# 1608_-_3.net
KiCad netlist of a schematic drawn in Altium Designer
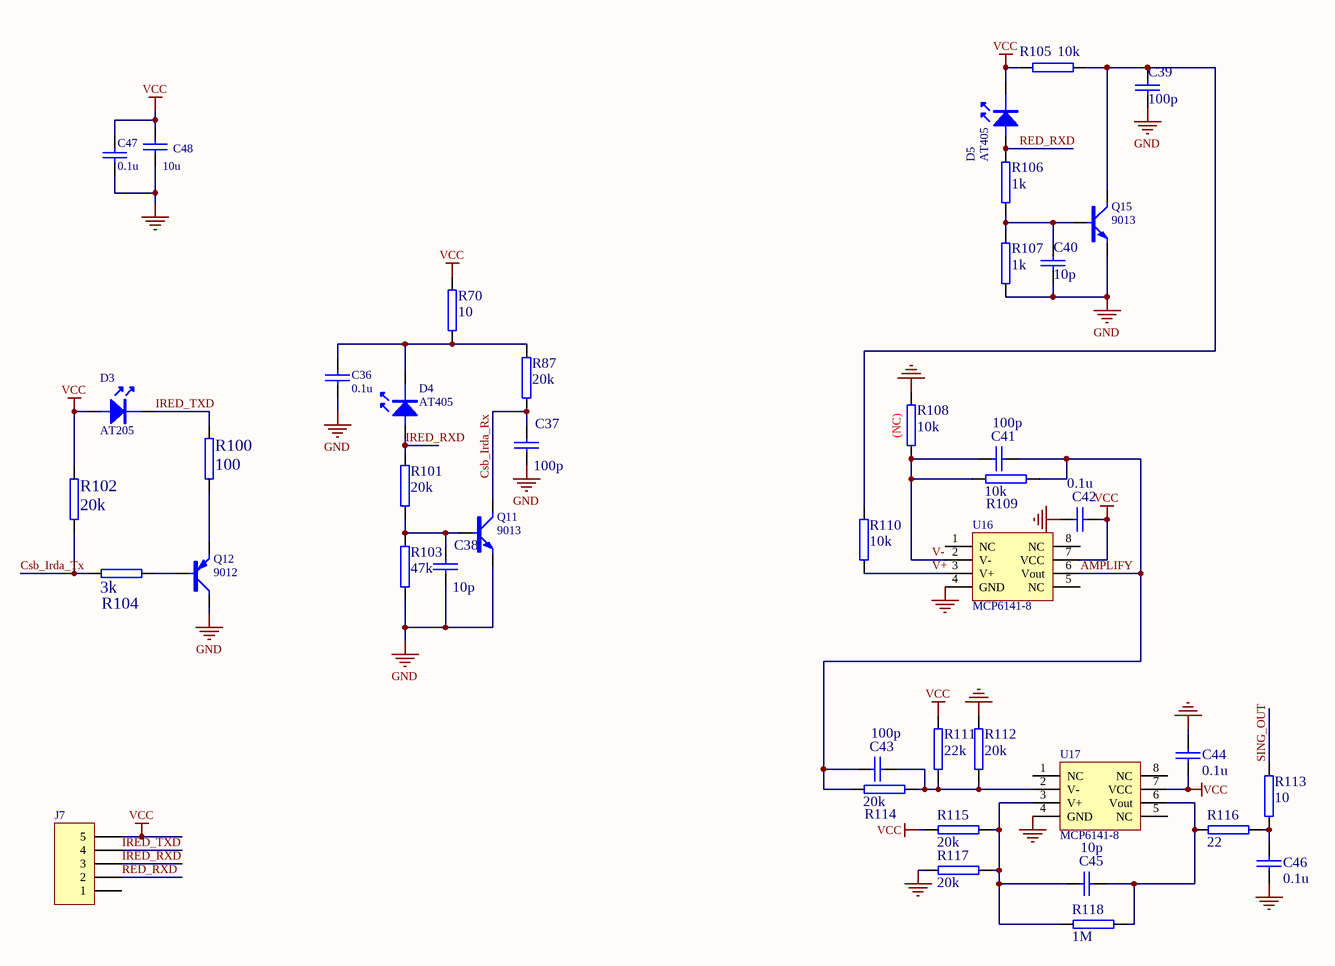
[diagram p0: 1608卡-原理图3.SchDoc]

(export (version "E")
  (design (tool "Eeschema 10.0.6"))
  (components
    (comp (ref "C36")
      (value "0.1u")
      (footprint "C0603")
      (description "无极性电容")
      (libsource (lib "CBB_Lib_SCH") (part "CAP"))
    )
    (comp (ref "C37")
      (value "100p")
      (footprint "C0603")
      (description "Capacitor")
      (libsource (lib "*") (part "CAP"))
    )
    (comp (ref "C38")
      (value "10p")
      (footprint "C0603")
      (description "Capacitor")
      (libsource (lib "*") (part "CAP"))
    )
    (comp (ref "C39")
      (value "100p")
      (footprint "C0603")
      (description "Capacitor")
      (libsource (lib "*") (part "CAP"))
    )
    (comp (ref "C40")
      (value "10p")
      (footprint "C0603")
      (description "Capacitor")
      (libsource (lib "*") (part "CAP"))
    )
    (comp (ref "C41")
      (value "100p")
      (footprint "C0603")
      (description "Capacitor")
      (libsource (lib "*") (part "CAP"))
    )
    (comp (ref "C42")
      (value "0.1u")
      (footprint "C0603")
      (description "Capacitor")
      (libsource (lib "*") (part "CAP"))
    )
    (comp (ref "C43")
      (value "100p")
      (footprint "C0603")
      (description "Capacitor")
      (libsource (lib "*") (part "CAP"))
    )
    (comp (ref "C44")
      (value "0.1u")
      (footprint "C0603")
      (description "Capacitor")
      (libsource (lib "*") (part "CAP"))
    )
    (comp (ref "C45")
      (value "10p")
      (footprint "C0603")
      (description "Capacitor")
      (libsource (lib "*") (part "CAP"))
    )
    (comp (ref "C46")
      (value "0.1u")
      (footprint "C0603")
      (description "Capacitor")
      (libsource (lib "*") (part "CAP"))
    )
    (comp (ref "C47")
      (value "0.1u")
      (footprint "C0603")
      (description "无极性电容")
      (libsource (lib "CBB_Lib_SCH") (part "CAP"))
    )
    (comp (ref "C48")
      (value "10u")
      (footprint "C0603")
      (description "无极性电容")
      (libsource (lib "CBB_Lib_SCH") (part "CAP"))
    )
    (comp (ref "D3") (value "AT205") (footprint "LEDRED") (libsource (lib "chip") (part "LED-5")))
    (comp (ref "D4") (value "AT405") (footprint "LEDRED") (libsource (lib "chip") (part "LED-5")))
    (comp (ref "D5") (value "AT405") (footprint "LEDRED") (libsource (lib "chip") (part "LED-5")))
    (comp (ref "J7")
      (value "TEM")
      (footprint "JP5")
      (description "Header, 5-Pin")
      (fields (field (name "PUBLISHER") "Altium Limited"))
      (libsource (lib "Miscellaneous Connectors") (part "Header 5"))
    )
    (comp (ref "Q11")
      (value "9013")
      (footprint "CBB_Lib_PCB:SOT-23-TRAN")
      (description "NPN Transistor")
      (libsource (lib "CBB_Lib_SCH") (part "NPN-S"))
    )
    (comp (ref "Q12") (value "9012") (footprint "SOT23-9013") (libsource (lib "chip") (part "9012")))
    (comp (ref "Q15")
      (value "9013")
      (footprint "CBB_Lib_PCB:SOT-23-TRAN")
      (description "NPN Transistor")
      (libsource (lib "CBB_Lib_SCH") (part "NPN-S"))
    )
    (comp (ref "R70") (value "10") (footprint "R0603") (libsource (lib "*") (part "RES11")))
    (comp (ref "R87") (value "20k") (footprint "R0603") (libsource (lib "*") (part "RES11")))
    (comp (ref "R100") (value "100") (footprint "R0603") (libsource (lib "*") (part "Pro28.tmp_UnNamed_37")))
    (comp (ref "R101") (value "20k") (footprint "R0603") (libsource (lib "*") (part "RES11")))
    (comp (ref "R102") (value "20k") (footprint "R0603") (libsource (lib "*") (part "Pro28.tmp_UnNamed_37")))
    (comp (ref "R103") (value "47k") (footprint "R0603") (libsource (lib "*") (part "RES11")))
    (comp (ref "R104") (value "3k") (footprint "R0603") (libsource (lib "*") (part "Pro28.tmp_UnNamed_37")))
    (comp (ref "R105") (value "10k") (footprint "R0603") (libsource (lib "*") (part "RES11")))
    (comp (ref "R106") (value "1k") (footprint "R0603") (libsource (lib "*") (part "RES11")))
    (comp (ref "R107") (value "1k") (footprint "R0603") (libsource (lib "*") (part "RES11")))
    (comp (ref "R108") (value "10k") (footprint "R0603") (libsource (lib "*") (part "RES11")))
    (comp (ref "R109") (value "10k") (footprint "R0603") (libsource (lib "*") (part "RES11")))
    (comp (ref "R110") (value "10k") (footprint "R0603") (libsource (lib "*") (part "RES11")))
    (comp (ref "R111") (value "22k") (footprint "R0603") (libsource (lib "*") (part "RES11")))
    (comp (ref "R112") (value "20k") (footprint "R0603") (libsource (lib "*") (part "RES11")))
    (comp (ref "R113") (value "10") (footprint "R0603") (libsource (lib "*") (part "RES11")))
    (comp (ref "R114") (value "20k") (footprint "R0603") (libsource (lib "*") (part "RES11")))
    (comp (ref "R115") (value "20k") (footprint "R0603") (libsource (lib "*") (part "RES11")))
    (comp (ref "R116") (value "22") (footprint "R0603") (libsource (lib "*") (part "RES11")))
    (comp (ref "R117") (value "20k") (footprint "R0603") (libsource (lib "*") (part "RES11")))
    (comp (ref "R118") (value "1M") (footprint "R0603") (libsource (lib "*") (part "RES11")))
    (comp (ref "U16") (value "MCP6141-8") (footprint "SO-8") (libsource (lib "*") (part "MCP6141-8")))
    (comp (ref "U17") (value "MCP6141-8") (footprint "SO-8") (libsource (lib "*") (part "MCP6141-8")))
  )
  (nets
    (net (code "1") (name "/AMPLIFY") (class "Default")
      (node (ref "C41") (pin "1") (pinfunction "1_1") (pintype "passive"))
      (node (ref "C43") (pin "2") (pinfunction "2_2") (pintype "passive"))
      (node (ref "R109") (pin "2") (pinfunction "2_2") (pintype "passive"))
      (node (ref "R114") (pin "1") (pinfunction "1_1") (pintype "passive"))
      (node (ref "U16") (pin "6") (pinfunction "Vout_6") (pintype "passive"))
    )
    (net (code "2") (name "/Csb_Irda_Rx") (class "Default")
      (node (ref "C37") (pin "1") (pinfunction "1_1") (pintype "passive"))
      (node (ref "Q11") (pin "C") (pinfunction "C_C") (pintype "passive"))
      (node (ref "R87") (pin "1") (pinfunction "1_1") (pintype "passive"))
    )
    (net (code "3") (name "/Csb_Irda_Tx") (class "Default")
      (node (ref "R102") (pin "2") (pintype "passive"))
      (node (ref "R104") (pin "2") (pintype "passive"))
    )
    (net (code "4") (name "/IRED_RXD") (class "Default")
      (node (ref "D4") (pin "1") (pinfunction "1_1") (pintype "passive"))
      (node (ref "J7") (pin "3") (pinfunction "3_3") (pintype "passive"))
      (node (ref "R101") (pin "1") (pinfunction "1_1") (pintype "passive"))
    )
    (net (code "5") (name "/IRED_TXD") (class "Default")
      (node (ref "D3") (pin "2") (pinfunction "2_2") (pintype "passive"))
      (node (ref "J7") (pin "4") (pinfunction "4_4") (pintype "passive"))
      (node (ref "R100") (pin "1") (pintype "passive"))
    )
    (net (code "6") (name "/RED_RXD") (class "Default")
      (node (ref "D5") (pin "1") (pinfunction "1_1") (pintype "passive"))
      (node (ref "J7") (pin "2") (pinfunction "2_2") (pintype "passive"))
      (node (ref "R106") (pin "1") (pinfunction "1_1") (pintype "passive"))
    )
    (net (code "7") (name "/SING_OUT") (class "Default")
      (node (ref "R113") (pin "1") (pinfunction "1_1") (pintype "passive"))
    )
    (net (code "8") (name "/V+") (class "Default")
      (node (ref "R110") (pin "2") (pinfunction "2_2") (pintype "passive"))
      (node (ref "U16") (pin "3") (pinfunction "V+_3") (pintype "passive"))
    )
    (net (code "9") (name "/V-") (class "Default")
      (node (ref "C41") (pin "2") (pinfunction "2_2") (pintype "passive"))
      (node (ref "R108") (pin "1") (pinfunction "1_1") (pintype "passive"))
      (node (ref "R109") (pin "1") (pinfunction "1_1") (pintype "passive"))
      (node (ref "U16") (pin "2") (pinfunction "V-_2") (pintype "passive"))
    )
    (net (code "10") (name "GND") (class "Default")
      (node (ref "C36") (pin "1") (pintype "passive"))
      (node (ref "C37") (pin "2") (pinfunction "2_2") (pintype "passive"))
      (node (ref "C38") (pin "2") (pinfunction "2_2") (pintype "passive"))
      (node (ref "C39") (pin "2") (pinfunction "2_2") (pintype "passive"))
      (node (ref "C40") (pin "2") (pinfunction "2_2") (pintype "passive"))
      (node (ref "C42") (pin "2") (pinfunction "2_2") (pintype "passive"))
      (node (ref "C44") (pin "2") (pinfunction "2_2") (pintype "passive"))
      (node (ref "C46") (pin "2") (pinfunction "2_2") (pintype "passive"))
      (node (ref "C47") (pin "2") (pintype "passive"))
      (node (ref "C48") (pin "2") (pintype "passive"))
      (node (ref "Q11") (pin "E") (pinfunction "E_E") (pintype "passive"))
      (node (ref "Q12") (pin "3") (pinfunction "C_3") (pintype "passive"))
      (node (ref "Q15") (pin "E") (pinfunction "E_E") (pintype "passive"))
      (node (ref "R103") (pin "2") (pinfunction "2_2") (pintype "passive"))
      (node (ref "R107") (pin "1") (pinfunction "1_1") (pintype "passive"))
      (node (ref "R108") (pin "2") (pinfunction "2_2") (pintype "passive"))
      (node (ref "R112") (pin "2") (pinfunction "2_2") (pintype "passive"))
      (node (ref "R117") (pin "2") (pinfunction "2_2") (pintype "passive"))
      (node (ref "U16") (pin "4") (pinfunction "GND_4") (pintype "passive"))
      (node (ref "U17") (pin "4") (pinfunction "GND_4") (pintype "passive"))
    )
    (net (code "11") (name "Net-(C36-Pad2)") (class "Default")
      (node (ref "C36") (pin "2") (pintype "passive"))
      (node (ref "D4") (pin "2") (pinfunction "2_2") (pintype "passive"))
      (node (ref "R70") (pin "1") (pinfunction "1_1") (pintype "passive"))
      (node (ref "R87") (pin "2") (pinfunction "2_2") (pintype "passive"))
    )
    (net (code "12") (name "Net-(C38-Pad1)") (class "Default")
      (node (ref "C38") (pin "1") (pinfunction "1_1") (pintype "passive"))
      (node (ref "Q11") (pin "B") (pinfunction "B_B") (pintype "passive"))
      (node (ref "R101") (pin "2") (pinfunction "2_2") (pintype "passive"))
      (node (ref "R103") (pin "1") (pinfunction "1_1") (pintype "passive"))
    )
    (net (code "13") (name "Net-(C39-Pad1)") (class "Default")
      (node (ref "C39") (pin "1") (pinfunction "1_1") (pintype "passive"))
      (node (ref "Q15") (pin "C") (pinfunction "C_C") (pintype "passive"))
      (node (ref "R105") (pin "1") (pinfunction "1_1") (pintype "passive"))
      (node (ref "R110") (pin "1") (pinfunction "1_1") (pintype "passive"))
    )
    (net (code "14") (name "Net-(C40-Pad1)") (class "Default")
      (node (ref "C40") (pin "1") (pinfunction "1_1") (pintype "passive"))
      (node (ref "Q15") (pin "B") (pinfunction "B_B") (pintype "passive"))
      (node (ref "R106") (pin "2") (pinfunction "2_2") (pintype "passive"))
      (node (ref "R107") (pin "2") (pinfunction "2_2") (pintype "passive"))
    )
    (net (code "15") (name "Net-(C46-Pad1)") (class "Default")
      (node (ref "C46") (pin "1") (pinfunction "1_1") (pintype "passive"))
      (node (ref "R113") (pin "2") (pinfunction "2_2") (pintype "passive"))
      (node (ref "R116") (pin "1") (pinfunction "1_1") (pintype "passive"))
    )
    (net (code "16") (name "Net-(Q12-B)") (class "Default")
      (node (ref "Q12") (pin "2") (pinfunction "B_2") (pintype "passive"))
      (node (ref "R104") (pin "1") (pintype "passive"))
    )
    (net (code "17") (name "Net-(Q12-E)") (class "Default")
      (node (ref "Q12") (pin "1") (pinfunction "E_1") (pintype "passive"))
      (node (ref "R100") (pin "2") (pintype "passive"))
    )
    (net (code "18") (name "Net-(U17-V+)") (class "Default")
      (node (ref "C45") (pin "2") (pinfunction "2_2") (pintype "passive"))
      (node (ref "R115") (pin "1") (pinfunction "1_1") (pintype "passive"))
      (node (ref "R117") (pin "1") (pinfunction "1_1") (pintype "passive"))
      (node (ref "R118") (pin "2") (pinfunction "2_2") (pintype "passive"))
      (node (ref "U17") (pin "3") (pinfunction "V+_3") (pintype "passive"))
    )
    (net (code "19") (name "Net-(U17-V-)") (class "Default")
      (node (ref "C43") (pin "1") (pinfunction "1_1") (pintype "passive"))
      (node (ref "R111") (pin "1") (pinfunction "1_1") (pintype "passive"))
      (node (ref "R112") (pin "1") (pinfunction "1_1") (pintype "passive"))
      (node (ref "R114") (pin "2") (pinfunction "2_2") (pintype "passive"))
      (node (ref "U17") (pin "2") (pinfunction "V-_2") (pintype "passive"))
    )
    (net (code "20") (name "Net-(U17-Vout)") (class "Default")
      (node (ref "C45") (pin "1") (pinfunction "1_1") (pintype "passive"))
      (node (ref "R116") (pin "2") (pinfunction "2_2") (pintype "passive"))
      (node (ref "R118") (pin "1") (pinfunction "1_1") (pintype "passive"))
      (node (ref "U17") (pin "6") (pinfunction "Vout_6") (pintype "passive"))
    )
    (net (code "21") (name "VCC") (class "Default")
      (node (ref "C42") (pin "1") (pinfunction "1_1") (pintype "passive"))
      (node (ref "C44") (pin "1") (pinfunction "1_1") (pintype "passive"))
      (node (ref "C47") (pin "1") (pintype "passive"))
      (node (ref "C48") (pin "1") (pintype "passive"))
      (node (ref "D3") (pin "1") (pinfunction "1_1") (pintype "passive"))
      (node (ref "D5") (pin "2") (pinfunction "2_2") (pintype "passive"))
      (node (ref "J7") (pin "5") (pinfunction "5_5") (pintype "passive"))
      (node (ref "R102") (pin "1") (pintype "passive"))
      (node (ref "R105") (pin "2") (pinfunction "2_2") (pintype "passive"))
      (node (ref "R111") (pin "2") (pinfunction "2_2") (pintype "passive"))
      (node (ref "R115") (pin "2") (pinfunction "2_2") (pintype "passive"))
      (node (ref "R70") (pin "2") (pinfunction "2_2") (pintype "passive"))
      (node (ref "U16") (pin "7") (pinfunction "VCC_7") (pintype "passive"))
      (node (ref "U17") (pin "7") (pinfunction "VCC_7") (pintype "passive"))
    )
    (net (code "22") (name "unconnected-(J7-Pad1)") (class "Default")
      (node (ref "J7") (pin "1") (pinfunction "1_1") (pintype "passive"))
    )
    (net (code "23") (name "unconnected-(U16-NC-Pad1)") (class "Default")
      (node (ref "U16") (pin "1") (pinfunction "NC_1") (pintype "passive"))
    )
    (net (code "24") (name "unconnected-(U16-NC-Pad5)") (class "Default")
      (node (ref "U16") (pin "5") (pinfunction "NC_5") (pintype "passive"))
    )
    (net (code "25") (name "unconnected-(U16-NC-Pad8)") (class "Default")
      (node (ref "U16") (pin "8") (pinfunction "NC_8") (pintype "passive"))
    )
    (net (code "26") (name "unconnected-(U17-NC-Pad1)") (class "Default")
      (node (ref "U17") (pin "1") (pinfunction "NC_1") (pintype "passive"))
    )
    (net (code "27") (name "unconnected-(U17-NC-Pad5)") (class "Default")
      (node (ref "U17") (pin "5") (pinfunction "NC_5") (pintype "passive"))
    )
    (net (code "28") (name "unconnected-(U17-NC-Pad8)") (class "Default")
      (node (ref "U17") (pin "8") (pinfunction "NC_8") (pintype "passive"))
    )
  )
)
